# LeftInterface.net
KiCad netlist of a schematic drawn in Altium Designer
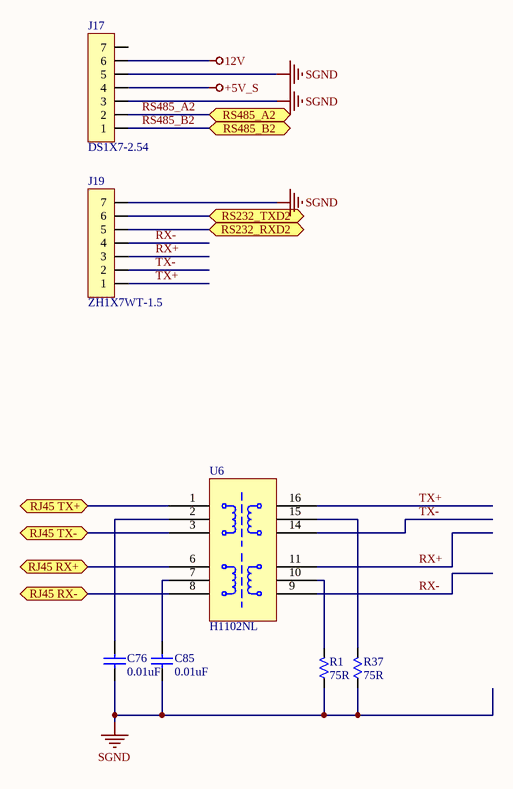
[diagram p0: LeftInterface.SchDoc]

(export (version "E")
  (design (tool "Eeschema 10.0.6"))
  (components
    (comp (ref "C76")
      (value "0.01uF")
      (footprint "C0805")
      (description "Capacitor")
      (fields (field (name "PUBLISHER") "Altium Limited"))
      (libsource (lib "Miscellaneous Devices") (part "Cap"))
    )
    (comp (ref "C85")
      (value "0.01uF")
      (footprint "C0805")
      (description "Capacitor")
      (fields (field (name "PUBLISHER") "Altium Limited"))
      (libsource (lib "Miscellaneous Devices") (part "Cap"))
    )
    (comp (ref "J17")
      (value "DS1X7-2.54")
      (footprint "DS1X7H-2.54")
      (libsource (lib "Connector Class") (part "HEADER1X7"))
    )
    (comp (ref "J19")
      (value "ZH1X7WT-1.5")
      (footprint "ZH1X7WT-1.5")
      (libsource (lib "Connector Class") (part "HEADER1X7"))
    )
    (comp (ref "R1")
      (value "75R")
      (footprint "R1206")
      (description "Resistor")
      (fields (field (name "PUBLISHER") "Altium Limited"))
      (libsource (lib "UP-Robot") (part "Res"))
    )
    (comp (ref "R37")
      (value "75R")
      (footprint "R1206")
      (description "Resistor")
      (fields (field (name "PUBLISHER") "Altium Limited"))
      (libsource (lib "UP-Robot") (part "Res"))
    )
    (comp (ref "U6")
      (value "H1102NL")
      (footprint "SOP16")
      (libsource (lib "Productor Class") (part "H1102NL"))
    )
  )
  (nets
    (net (code "1") (name "+5V_S") (class "Default")
      (node (ref "J17") (pin "4") (pinfunction "4_4") (pintype "passive"))
    )
    (net (code "2") (name "/RJ45 RX+") (class "Default") (node (ref "U6") (pin "6") (pintype "passive")))
    (net (code "3") (name "/RJ45 RX-") (class "Default") (node (ref "U6") (pin "8") (pintype "passive")))
    (net (code "4") (name "/RJ45 TX+") (class "Default") (node (ref "U6") (pin "1") (pintype "passive")))
    (net (code "5") (name "/RJ45 TX-") (class "Default") (node (ref "U6") (pin "3") (pintype "passive")))
    (net (code "6") (name "/RS232_RXD2") (class "Default")
      (node (ref "J19") (pin "5") (pinfunction "5_5") (pintype "passive"))
    )
    (net (code "7") (name "/RS232_TXD2") (class "Default")
      (node (ref "J19") (pin "6") (pinfunction "6_6") (pintype "passive"))
    )
    (net (code "8") (name "/RS485_A2") (class "Default")
      (node (ref "J17") (pin "2") (pinfunction "2_2") (pintype "passive"))
    )
    (net (code "9") (name "/RS485_B2") (class "Default")
      (node (ref "J17") (pin "1") (pinfunction "1_1") (pintype "passive"))
    )
    (net (code "10") (name "/RX+") (class "Default")
      (node (ref "J19") (pin "3") (pinfunction "3_3") (pintype "passive"))
      (node (ref "U6") (pin "11") (pintype "passive"))
    )
    (net (code "11") (name "/RX-") (class "Default")
      (node (ref "J19") (pin "4") (pinfunction "4_4") (pintype "passive"))
      (node (ref "U6") (pin "9") (pintype "passive"))
    )
    (net (code "12") (name "/TX+") (class "Default")
      (node (ref "J19") (pin "1") (pinfunction "1_1") (pintype "passive"))
      (node (ref "U6") (pin "16") (pintype "passive"))
    )
    (net (code "13") (name "/TX-") (class "Default")
      (node (ref "J19") (pin "2") (pinfunction "2_2") (pintype "passive"))
      (node (ref "U6") (pin "14") (pintype "passive"))
    )
    (net (code "14") (name "12V") (class "Default")
      (node (ref "J17") (pin "6") (pinfunction "6_6") (pintype "passive"))
    )
    (net (code "15") (name "Net-(C76-Pad1)") (class "Default")
      (node (ref "C76") (pin "1") (pinfunction "1_1") (pintype "passive"))
      (node (ref "U6") (pin "2") (pintype "passive"))
    )
    (net (code "16") (name "Net-(C85-Pad1)") (class "Default")
      (node (ref "C85") (pin "1") (pinfunction "1_1") (pintype "passive"))
      (node (ref "U6") (pin "7") (pintype "passive"))
    )
    (net (code "17") (name "Net-(R1-Pad1)") (class "Default")
      (node (ref "R1") (pin "1") (pinfunction "1_1") (pintype "passive"))
      (node (ref "U6") (pin "10") (pintype "passive"))
    )
    (net (code "18") (name "Net-(R37-Pad1)") (class "Default")
      (node (ref "R37") (pin "1") (pinfunction "1_1") (pintype "passive"))
      (node (ref "U6") (pin "15") (pintype "passive"))
    )
    (net (code "19") (name "SGND") (class "Default")
      (node (ref "C76") (pin "2") (pinfunction "2_2") (pintype "passive"))
      (node (ref "C85") (pin "2") (pinfunction "2_2") (pintype "passive"))
      (node (ref "J17") (pin "3") (pinfunction "3_3") (pintype "passive"))
      (node (ref "J17") (pin "5") (pinfunction "5_5") (pintype "passive"))
      (node (ref "J19") (pin "7") (pinfunction "7_7") (pintype "passive"))
      (node (ref "R1") (pin "2") (pinfunction "2_2") (pintype "passive"))
      (node (ref "R37") (pin "2") (pinfunction "2_2") (pintype "passive"))
    )
    (net (code "20") (name "unconnected-(J17-Pad7)") (class "Default")
      (node (ref "J17") (pin "7") (pinfunction "7_7") (pintype "passive"))
    )
  )
)
